# plantshield_huzzah.net
KiCad netlist of a schematic drawn in EAGLE
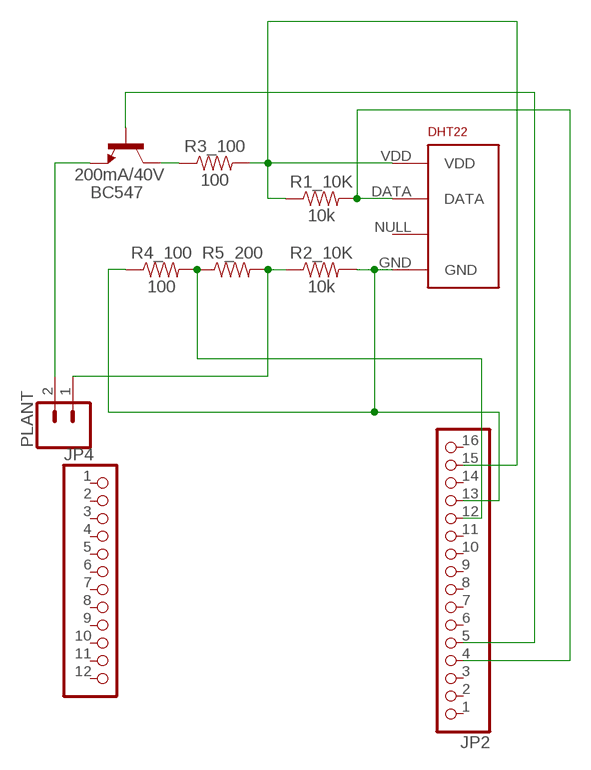
[diagram p0: schematic, sheet 1]

(export (version "E")
  (design (tool "Eeschema 10.0.6"))
  (components
    (comp (ref "BC547")
      (value "200mA/40V")
      (footprint "eagle-import:TO-92")
      (libsource (lib "eagle-import") (part "TRANS_NPN-2N3904"))
    )
    (comp (ref "DHT22")
      (value "RHT03_DHT-22_AM2302")
      (footprint "eagle-import:RHT03_DHT-22")
      (libsource (lib "eagle-import") (part "RHT03_DHT-22_AM2302"))
    )
    (comp (ref "JP2")
      (value "HEADER-1X16ROUND")
      (footprint "eagle-import:1X16_ROUND")
      (libsource (lib "eagle-import") (part "HEADER-1X16ROUND"))
    )
    (comp (ref "JP4")
      (value "HEADER-1X12")
      (footprint "eagle-import:1X12_ROUND")
      (libsource (lib "eagle-import") (part "HEADER-1X12"))
    )
    (comp (ref "PLANT")
      (value "CONN_02")
      (footprint "eagle-import:1X02")
      (libsource (lib "eagle-import") (part "CONN_02"))
    )
    (comp (ref "R1_10K")
      (value "10k")
      (footprint "eagle-import:AXIAL-0.3")
      (libsource (lib "eagle-import") (part "10KOHM-HORIZ-1/4W-1%"))
    )
    (comp (ref "R2_10K")
      (value "10k")
      (footprint "eagle-import:AXIAL-0.3")
      (libsource (lib "eagle-import") (part "10KOHM-HORIZ-1/4W-1%"))
    )
    (comp (ref "R3_100")
      (value "100")
      (footprint "eagle-import:AXIAL-0.3")
      (libsource (lib "eagle-import") (part "100OHM-HORIZ-1/4W-1%"))
    )
    (comp (ref "R4_100")
      (value "100")
      (footprint "eagle-import:AXIAL-0.3")
      (libsource (lib "eagle-import") (part "100OHM-HORIZ-1/4W-1%"))
    )
    (comp (ref "R5_200")
      (value "RESISTORAXIAL-0.3")
      (footprint "eagle-import:AXIAL-0.3")
      (libsource (lib "eagle-import") (part "RESISTORAXIAL-0.3"))
    )
  )
  (nets
    (net (code "1") (name "Net-(BC547-B)") (class "Default")
      (node (ref "BC547") (pin "2") (pinfunction "B_2") (pintype "passive"))
      (node (ref "JP2") (pin "5") (pinfunction "5_5") (pintype "passive"))
    )
    (net (code "2") (name "Net-(BC547-C)") (class "Default")
      (node (ref "BC547") (pin "3") (pinfunction "C_3") (pintype "passive"))
      (node (ref "R3_100") (pin "P$1") (pinfunction "1_P$1") (pintype "passive"))
    )
    (net (code "3") (name "Net-(BC547-E)") (class "Default")
      (node (ref "BC547") (pin "1") (pinfunction "E_1") (pintype "passive"))
      (node (ref "PLANT") (pin "2") (pinfunction "2_2") (pintype "passive"))
    )
    (net (code "4") (name "Net-(R1_10K-1)") (class "Default")
      (node (ref "DHT22") (pin "VDD") (pinfunction "VDD_VDD") (pintype "power_in"))
      (node (ref "JP2") (pin "15") (pinfunction "15_15") (pintype "passive"))
      (node (ref "R1_10K") (pin "P$1") (pinfunction "1_P$1") (pintype "passive"))
      (node (ref "R3_100") (pin "P$2") (pinfunction "2_P$2") (pintype "passive"))
    )
    (net (code "5") (name "Net-(R1_10K-2)") (class "Default")
      (node (ref "DHT22") (pin "DATA") (pinfunction "DATA_DATA") (pintype "bidirectional"))
      (node (ref "JP2") (pin "4") (pinfunction "4_4") (pintype "passive"))
      (node (ref "R1_10K") (pin "P$2") (pinfunction "2_P$2") (pintype "passive"))
    )
    (net (code "6") (name "Net-(R2_10K-1)") (class "Default")
      (node (ref "PLANT") (pin "1") (pinfunction "1_1") (pintype "passive"))
      (node (ref "R2_10K") (pin "P$1") (pinfunction "1_P$1") (pintype "passive"))
      (node (ref "R5_200") (pin "P$2") (pinfunction "2_P$2") (pintype "passive"))
    )
    (net (code "7") (name "Net-(R2_10K-2)") (class "Default")
      (node (ref "DHT22") (pin "GND") (pinfunction "GND_GND") (pintype "power_in"))
      (node (ref "JP2") (pin "13") (pinfunction "13_13") (pintype "passive"))
      (node (ref "R2_10K") (pin "P$2") (pinfunction "2_P$2") (pintype "passive"))
      (node (ref "R4_100") (pin "P$1") (pinfunction "1_P$1") (pintype "passive"))
    )
    (net (code "8") (name "Net-(R4_100-2)") (class "Default")
      (node (ref "JP2") (pin "12") (pinfunction "12_12") (pintype "passive"))
      (node (ref "R4_100") (pin "P$2") (pinfunction "2_P$2") (pintype "passive"))
      (node (ref "R5_200") (pin "P$1") (pinfunction "1_P$1") (pintype "passive"))
    )
    (net (code "9") (name "unconnected-(DHT22-PadNULL)") (class "Default")
      (node (ref "DHT22") (pin "NULL") (pinfunction "NULL_NULL") (pintype "no_connect"))
    )
    (net (code "10") (name "unconnected-(JP2-Pad1)") (class "Default")
      (node (ref "JP2") (pin "1") (pinfunction "1_1") (pintype "passive"))
    )
    (net (code "11") (name "unconnected-(JP2-Pad2)") (class "Default")
      (node (ref "JP2") (pin "2") (pinfunction "2_2") (pintype "passive"))
    )
    (net (code "12") (name "unconnected-(JP2-Pad3)") (class "Default")
      (node (ref "JP2") (pin "3") (pinfunction "3_3") (pintype "passive"))
    )
    (net (code "13") (name "unconnected-(JP2-Pad6)") (class "Default")
      (node (ref "JP2") (pin "6") (pinfunction "6_6") (pintype "passive"))
    )
    (net (code "14") (name "unconnected-(JP2-Pad7)") (class "Default")
      (node (ref "JP2") (pin "7") (pinfunction "7_7") (pintype "passive"))
    )
    (net (code "15") (name "unconnected-(JP2-Pad8)") (class "Default")
      (node (ref "JP2") (pin "8") (pinfunction "8_8") (pintype "passive"))
    )
    (net (code "16") (name "unconnected-(JP2-Pad9)") (class "Default")
      (node (ref "JP2") (pin "9") (pinfunction "9_9") (pintype "passive"))
    )
    (net (code "17") (name "unconnected-(JP2-Pad10)") (class "Default")
      (node (ref "JP2") (pin "10") (pinfunction "10_10") (pintype "passive"))
    )
    (net (code "18") (name "unconnected-(JP2-Pad11)") (class "Default")
      (node (ref "JP2") (pin "11") (pinfunction "11_11") (pintype "passive"))
    )
    (net (code "19") (name "unconnected-(JP2-Pad14)") (class "Default")
      (node (ref "JP2") (pin "14") (pinfunction "14_14") (pintype "passive"))
    )
    (net (code "20") (name "unconnected-(JP2-Pad16)") (class "Default")
      (node (ref "JP2") (pin "16") (pinfunction "16_16") (pintype "passive"))
    )
    (net (code "21") (name "unconnected-(JP4-Pad1)") (class "Default")
      (node (ref "JP4") (pin "1") (pinfunction "1_1") (pintype "passive"))
    )
    (net (code "22") (name "unconnected-(JP4-Pad2)") (class "Default")
      (node (ref "JP4") (pin "2") (pinfunction "2_2") (pintype "passive"))
    )
    (net (code "23") (name "unconnected-(JP4-Pad3)") (class "Default")
      (node (ref "JP4") (pin "3") (pinfunction "3_3") (pintype "passive"))
    )
    (net (code "24") (name "unconnected-(JP4-Pad4)") (class "Default")
      (node (ref "JP4") (pin "4") (pinfunction "4_4") (pintype "passive"))
    )
    (net (code "25") (name "unconnected-(JP4-Pad5)") (class "Default")
      (node (ref "JP4") (pin "5") (pinfunction "5_5") (pintype "passive"))
    )
    (net (code "26") (name "unconnected-(JP4-Pad6)") (class "Default")
      (node (ref "JP4") (pin "6") (pinfunction "6_6") (pintype "passive"))
    )
    (net (code "27") (name "unconnected-(JP4-Pad7)") (class "Default")
      (node (ref "JP4") (pin "7") (pinfunction "7_7") (pintype "passive"))
    )
    (net (code "28") (name "unconnected-(JP4-Pad8)") (class "Default")
      (node (ref "JP4") (pin "8") (pinfunction "8_8") (pintype "passive"))
    )
    (net (code "29") (name "unconnected-(JP4-Pad9)") (class "Default")
      (node (ref "JP4") (pin "9") (pinfunction "9_9") (pintype "passive"))
    )
    (net (code "30") (name "unconnected-(JP4-Pad10)") (class "Default")
      (node (ref "JP4") (pin "10") (pinfunction "10_10") (pintype "passive"))
    )
    (net (code "31") (name "unconnected-(JP4-Pad11)") (class "Default")
      (node (ref "JP4") (pin "11") (pinfunction "11_11") (pintype "passive"))
    )
    (net (code "32") (name "unconnected-(JP4-Pad12)") (class "Default")
      (node (ref "JP4") (pin "12") (pinfunction "12_12") (pintype "passive"))
    )
  )
)
